# PIXRACER-FMU-R12.net
KiCad netlist of a schematic drawn in Altium Designer
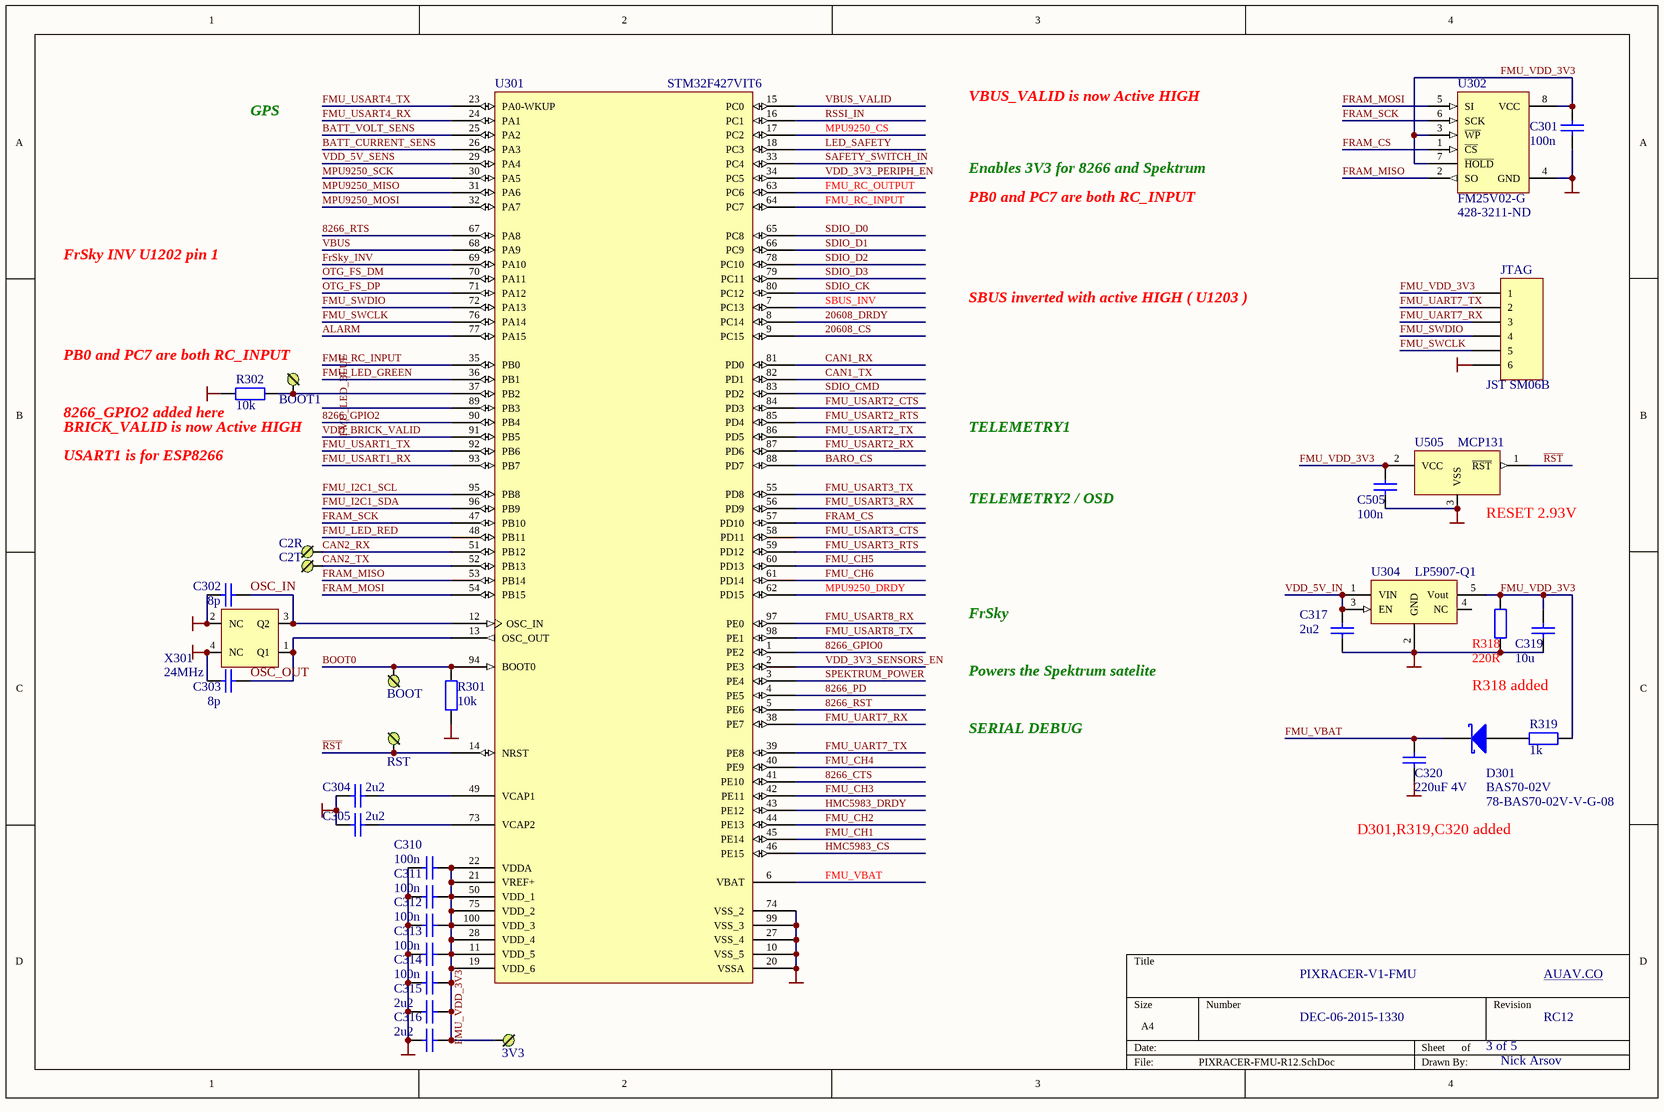
[diagram p0: PIXRACER-FMU-R12.SchDoc]

(export (version "E")
  (design (tool "Eeschema 10.0.6"))
  (components
    (comp (ref "3V3") (value "3V3") (footprint "PAD1") (libsource (lib "My_Altium") (part "PLUG")))
    (comp (ref "BOOT") (value "BOOT") (footprint "PAD1") (libsource (lib "My_Altium") (part "PLUG")))
    (comp (ref "BOOT1") (value "BOOT1") (footprint "PAD1") (libsource (lib "My_Altium") (part "PLUG")))
    (comp (ref "C2R") (value "CAN2_RX") (footprint "PAD1") (libsource (lib "My_Altium") (part "PLUG")))
    (comp (ref "C2T") (value "CAN2_TX") (footprint "PAD1") (libsource (lib "My_Altium") (part "PLUG")))
    (comp (ref "C301")
      (value "100n")
      (footprint "0402A")
      (description "Capacitor")
      (fields (field (name "PUBLISHER") "Altium Limited"))
      (libsource (lib "Miscellaneous Devices") (part "Cap"))
    )
    (comp (ref "C302")
      (value "8p")
      (footprint "0603A")
      (description "Capacitor")
      (fields (field (name "PUBLISHER") "Altium Limited"))
      (libsource (lib "Miscellaneous Devices") (part "Cap"))
    )
    (comp (ref "C303")
      (value "8p")
      (footprint "0603A")
      (description "Capacitor")
      (fields (field (name "PUBLISHER") "Altium Limited"))
      (libsource (lib "Miscellaneous Devices") (part "Cap"))
    )
    (comp (ref "C304")
      (value "2u2")
      (footprint "0402A")
      (description "Capacitor")
      (fields (field (name "PUBLISHER") "Altium Limited"))
      (libsource (lib "Miscellaneous Devices") (part "Cap"))
    )
    (comp (ref "C305")
      (value "2u2")
      (footprint "0402A")
      (description "Capacitor")
      (fields (field (name "PUBLISHER") "Altium Limited"))
      (libsource (lib "Miscellaneous Devices") (part "Cap"))
    )
    (comp (ref "C310")
      (value "100n")
      (footprint "0402A")
      (description "Capacitor")
      (fields (field (name "PUBLISHER") "Altium Limited"))
      (libsource (lib "Miscellaneous Devices") (part "Cap"))
    )
    (comp (ref "C311")
      (value "100n")
      (footprint "0402A")
      (description "Capacitor")
      (fields (field (name "PUBLISHER") "Altium Limited"))
      (libsource (lib "Miscellaneous Devices") (part "Cap"))
    )
    (comp (ref "C312")
      (value "100n")
      (footprint "0402A")
      (description "Capacitor")
      (fields (field (name "PUBLISHER") "Altium Limited"))
      (libsource (lib "Miscellaneous Devices") (part "Cap"))
    )
    (comp (ref "C313")
      (value "100n")
      (footprint "0402A")
      (description "Capacitor")
      (fields (field (name "PUBLISHER") "Altium Limited"))
      (libsource (lib "Miscellaneous Devices") (part "Cap"))
    )
    (comp (ref "C314")
      (value "100n")
      (footprint "0402A")
      (description "Capacitor")
      (fields (field (name "PUBLISHER") "Altium Limited"))
      (libsource (lib "Miscellaneous Devices") (part "Cap"))
    )
    (comp (ref "C315")
      (value "2u2")
      (footprint "0402A")
      (description "Capacitor")
      (fields (field (name "PUBLISHER") "Altium Limited"))
      (libsource (lib "Miscellaneous Devices") (part "Cap"))
    )
    (comp (ref "C316")
      (value "2u2")
      (footprint "0402A")
      (description "Capacitor")
      (fields (field (name "PUBLISHER") "Altium Limited"))
      (libsource (lib "Miscellaneous Devices") (part "Cap"))
    )
    (comp (ref "C317")
      (value "2u2")
      (footprint "0603A")
      (description "Capacitor")
      (fields (field (name "PUBLISHER") "Altium Limited"))
      (libsource (lib "Miscellaneous Devices") (part "Cap"))
    )
    (comp (ref "C319")
      (value "10u")
      (footprint "0603A")
      (description "Capacitor")
      (fields (field (name "PUBLISHER") "Altium Limited"))
      (libsource (lib "Miscellaneous Devices") (part "Cap"))
    )
    (comp (ref "C320")
      (value "220uF 4V")
      (footprint "1206A")
      (description "Capacitor")
      (fields (field (name "PUBLISHER") "Altium Limited"))
      (libsource (lib "Miscellaneous Devices") (part "Cap"))
    )
    (comp (ref "C505")
      (value "100n")
      (footprint "0402A")
      (description "Capacitor")
      (fields (field (name "PUBLISHER") "Altium Limited"))
      (libsource (lib "Miscellaneous Devices") (part "Cap"))
    )
    (comp (ref "D301")
      (value "BAS70-02V")
      (footprint "SOD-523")
      (description "Schottky Diode")
      (fields (field (name "MOUSER") "78-BAS70-02V-V-G-08") (field (name "PUBLISHER") "Altium Limited"))
      (libsource (lib "Miscellaneous Devices") (part "D Schottky"))
    )
    (comp (ref "JTAG")
      (value "JST SM06B")
      (footprint "SM06B-SRSH-TB")
      (description "Header, 6-Pin")
      (fields (field (name "PUBLISHER") "Altium Limited"))
      (libsource (lib "Miscellaneous Connectors") (part "Header 6"))
    )
    (comp (ref "R301")
      (value "10k")
      (footprint "0402A")
      (description "Resistor")
      (fields (field (name "PUBLISHER") "Altium Limited"))
      (libsource (lib "") (part "Res2_3"))
    )
    (comp (ref "R302")
      (value "10k")
      (footprint "0402A")
      (description "Resistor")
      (fields (field (name "PUBLISHER") "Altium Limited"))
      (libsource (lib "Miscellaneous Devices") (part "Res2"))
    )
    (comp (ref "R318")
      (value "220R")
      (footprint "0603A")
      (description "Resistor")
      (fields (field (name "PUBLISHER") "Altium Limited"))
      (libsource (lib "") (part "Res2_2"))
    )
    (comp (ref "R319")
      (value "1k")
      (footprint "0603A")
      (description "Resistor")
      (fields (field (name "PUBLISHER") "Altium Limited"))
      (libsource (lib "") (part "Res2_1"))
    )
    (comp (ref "RST") (value "BOOT") (footprint "PAD1") (libsource (lib "My_Altium") (part "PLUG")))
    (comp (ref "U301")
      (value "STM32F427VIT6")
      (footprint "LQFP100_L")
      (description "STM32 ARM-based 32-bit MCU with 64 Kbytes Flash, 100-pin LQFP, Industrial Temperature")
      (fields (field (name "PUBLISHER") "Altium Limited"))
      (libsource (lib "ST Microcontroller 32-Bit STM32") (part "STM32F103VBT6"))
    )
    (comp (ref "U302")
      (value "FM25V02-G")
      (footprint "SO-8_N")
      (fields (field (name "SUPPLIER PART NUMBER") "428-3211-ND"))
      (libsource (lib "My_Altium") (part "AT45DB161D-MU"))
    )
    (comp (ref "U304")
      (value "LP5907-Q1")
      (footprint "SOT23-5")
      (libsource (lib "My_Altium") (part "LP5907-Q1"))
    )
    (comp (ref "U505") (value "MCP131") (footprint "SOT-323") (libsource (lib "My_Altium") (part "MCP102")))
    (comp (ref "X301")
      (value "24MHz")
      (footprint "Crystal_2.5x2")
      (libsource (lib "My_Altium") (part "Crystal_4pin"))
    )
  )
  (nets
    (net (code "1") (name "/8266_CTS") (class "Default")
      (node (ref "U301") (pin "41") (pinfunction "PE10_41") (pintype "bidirectional"))
    )
    (net (code "2") (name "/8266_GPIO0") (class "Default")
      (node (ref "U301") (pin "1") (pinfunction "PE2_1") (pintype "bidirectional"))
    )
    (net (code "3") (name "/8266_GPIO2") (class "Default")
      (node (ref "U301") (pin "90") (pinfunction "PB4_90") (pintype "bidirectional"))
    )
    (net (code "4") (name "/8266_PD") (class "Default")
      (node (ref "U301") (pin "4") (pinfunction "PE5_4") (pintype "bidirectional"))
    )
    (net (code "5") (name "/8266_RST") (class "Default")
      (node (ref "U301") (pin "5") (pinfunction "PE6_5") (pintype "bidirectional"))
    )
    (net (code "6") (name "/8266_RTS") (class "Default")
      (node (ref "U301") (pin "67") (pinfunction "PA8_67") (pintype "bidirectional"))
    )
    (net (code "7") (name "/20608_CS") (class "Default")
      (node (ref "U301") (pin "9") (pinfunction "PC15_9") (pintype "bidirectional"))
    )
    (net (code "8") (name "/20608_DRDY") (class "Default")
      (node (ref "U301") (pin "8") (pinfunction "PC14_8") (pintype "bidirectional"))
    )
    (net (code "9") (name "/ALARM") (class "Default")
      (node (ref "U301") (pin "77") (pinfunction "PA15_77") (pintype "bidirectional"))
    )
    (net (code "10") (name "/BARO_CS") (class "Default")
      (node (ref "U301") (pin "88") (pinfunction "PD7_88") (pintype "bidirectional"))
    )
    (net (code "11") (name "/BATT_CURRENT_SENS") (class "Default")
      (node (ref "U301") (pin "26") (pinfunction "PA3_26") (pintype "bidirectional"))
    )
    (net (code "12") (name "/BATT_VOLT_SENS") (class "Default")
      (node (ref "U301") (pin "25") (pinfunction "PA2_25") (pintype "bidirectional"))
    )
    (net (code "13") (name "/BOOT0") (class "Default")
      (node (ref "BOOT") (pin "1") (pintype "passive"))
      (node (ref "R301") (pin "1") (pinfunction "1_1") (pintype "passive"))
      (node (ref "U301") (pin "94") (pinfunction "BOOT0_94") (pintype "input"))
    )
    (net (code "14") (name "/CAN1_RX") (class "Default")
      (node (ref "U301") (pin "81") (pinfunction "PD0_81") (pintype "bidirectional"))
    )
    (net (code "15") (name "/CAN1_TX") (class "Default")
      (node (ref "U301") (pin "82") (pinfunction "PD1_82") (pintype "bidirectional"))
    )
    (net (code "16") (name "/CAN2_RX") (class "Default")
      (node (ref "C2R") (pin "1") (pintype "passive"))
      (node (ref "U301") (pin "51") (pinfunction "PB12_51") (pintype "bidirectional"))
    )
    (net (code "17") (name "/CAN2_TX") (class "Default")
      (node (ref "C2T") (pin "1") (pintype "passive"))
      (node (ref "U301") (pin "52") (pinfunction "PB13_52") (pintype "bidirectional"))
    )
    (net (code "18") (name "/FMU_CH1") (class "Default")
      (node (ref "U301") (pin "45") (pinfunction "PE14_45") (pintype "bidirectional"))
    )
    (net (code "19") (name "/FMU_CH2") (class "Default")
      (node (ref "U301") (pin "44") (pinfunction "PE13_44") (pintype "bidirectional"))
    )
    (net (code "20") (name "/FMU_CH3") (class "Default")
      (node (ref "U301") (pin "42") (pinfunction "PE11_42") (pintype "bidirectional"))
    )
    (net (code "21") (name "/FMU_CH4") (class "Default")
      (node (ref "U301") (pin "40") (pinfunction "PE9_40") (pintype "bidirectional"))
    )
    (net (code "22") (name "/FMU_CH5") (class "Default")
      (node (ref "U301") (pin "60") (pinfunction "PD13_60") (pintype "bidirectional"))
    )
    (net (code "23") (name "/FMU_CH6") (class "Default")
      (node (ref "U301") (pin "61") (pinfunction "PD14_61") (pintype "bidirectional"))
    )
    (net (code "24") (name "/FMU_I2C1_SCL") (class "Default")
      (node (ref "U301") (pin "95") (pinfunction "PB8_95") (pintype "bidirectional"))
    )
    (net (code "25") (name "/FMU_I2C1_SDA") (class "Default")
      (node (ref "U301") (pin "96") (pinfunction "PB9_96") (pintype "bidirectional"))
    )
    (net (code "26") (name "/FMU_LED_BLUE") (class "Default")
      (node (ref "U301") (pin "91") (pinfunction "PB5_91") (pintype "bidirectional"))
    )
    (net (code "27") (name "/FMU_LED_GREEN") (class "Default")
      (node (ref "U301") (pin "36") (pinfunction "PB1_36") (pintype "bidirectional"))
    )
    (net (code "28") (name "/FMU_LED_RED") (class "Default")
      (node (ref "U301") (pin "48") (pinfunction "PB11_48") (pintype "bidirectional"))
    )
    (net (code "29") (name "/FMU_RC_INPUT") (class "Default")
      (node (ref "U301") (pin "35") (pinfunction "PB0_35") (pintype "bidirectional"))
      (node (ref "U301") (pin "64") (pinfunction "PC7_64") (pintype "bidirectional"))
    )
    (net (code "30") (name "/FMU_RC_OUTPUT") (class "Default")
      (node (ref "U301") (pin "63") (pinfunction "PC6_63") (pintype "bidirectional"))
    )
    (net (code "31") (name "/FMU_SWCLK") (class "Default")
      (node (ref "JTAG") (pin "5") (pinfunction "5_5") (pintype "passive"))
      (node (ref "U301") (pin "76") (pinfunction "PA14_76") (pintype "bidirectional"))
    )
    (net (code "32") (name "/FMU_SWDIO") (class "Default")
      (node (ref "JTAG") (pin "4") (pinfunction "4_4") (pintype "passive"))
      (node (ref "U301") (pin "72") (pinfunction "PA13_72") (pintype "bidirectional"))
    )
    (net (code "33") (name "/FMU_UART7_RX") (class "Default")
      (node (ref "JTAG") (pin "3") (pinfunction "3_3") (pintype "passive"))
      (node (ref "U301") (pin "38") (pinfunction "PE7_38") (pintype "bidirectional"))
    )
    (net (code "34") (name "/FMU_UART7_TX") (class "Default")
      (node (ref "JTAG") (pin "2") (pinfunction "2_2") (pintype "passive"))
      (node (ref "U301") (pin "39") (pinfunction "PE8_39") (pintype "bidirectional"))
    )
    (net (code "35") (name "/FMU_USART1_RX") (class "Default")
      (node (ref "U301") (pin "93") (pinfunction "PB7_93") (pintype "bidirectional"))
    )
    (net (code "36") (name "/FMU_USART1_TX") (class "Default")
      (node (ref "U301") (pin "92") (pinfunction "PB6_92") (pintype "bidirectional"))
    )
    (net (code "37") (name "/FMU_USART2_CTS") (class "Default")
      (node (ref "U301") (pin "84") (pinfunction "PD3_84") (pintype "bidirectional"))
    )
    (net (code "38") (name "/FMU_USART2_RTS") (class "Default")
      (node (ref "U301") (pin "85") (pinfunction "PD4_85") (pintype "bidirectional"))
    )
    (net (code "39") (name "/FMU_USART2_RX") (class "Default")
      (node (ref "U301") (pin "87") (pinfunction "PD6_87") (pintype "bidirectional"))
    )
    (net (code "40") (name "/FMU_USART2_TX") (class "Default")
      (node (ref "U301") (pin "86") (pinfunction "PD5_86") (pintype "bidirectional"))
    )
    (net (code "41") (name "/FMU_USART3_CTS") (class "Default")
      (node (ref "U301") (pin "58") (pinfunction "PD11_58") (pintype "bidirectional"))
    )
    (net (code "42") (name "/FMU_USART3_RTS") (class "Default")
      (node (ref "U301") (pin "59") (pinfunction "PD12_59") (pintype "bidirectional"))
    )
    (net (code "43") (name "/FMU_USART3_RX") (class "Default")
      (node (ref "U301") (pin "56") (pinfunction "PD9_56") (pintype "bidirectional"))
    )
    (net (code "44") (name "/FMU_USART3_TX") (class "Default")
      (node (ref "U301") (pin "55") (pinfunction "PD8_55") (pintype "bidirectional"))
    )
    (net (code "45") (name "/FMU_USART4_RX") (class "Default")
      (node (ref "U301") (pin "24") (pinfunction "PA1_24") (pintype "bidirectional"))
    )
    (net (code "46") (name "/FMU_USART4_TX") (class "Default")
      (node (ref "U301") (pin "23") (pinfunction "PA0-WKUP_23") (pintype "bidirectional"))
    )
    (net (code "47") (name "/FMU_USART8_RX") (class "Default")
      (node (ref "U301") (pin "97") (pinfunction "PE0_97") (pintype "bidirectional"))
    )
    (net (code "48") (name "/FMU_USART8_TX") (class "Default")
      (node (ref "U301") (pin "98") (pinfunction "PE1_98") (pintype "bidirectional"))
    )
    (net (code "49") (name "/FMU_VBAT") (class "Default")
      (node (ref "C320") (pin "2") (pinfunction "2_2") (pintype "passive"))
      (node (ref "D301") (pin "2") (pinfunction "K_2") (pintype "passive"))
      (node (ref "U301") (pin "6") (pinfunction "VBAT_6") (pintype "power_in"))
    )
    (net (code "50") (name "/FMU_VDD_3V3") (class "Default")
      (node (ref "3V3") (pin "1") (pintype "passive"))
      (node (ref "C301") (pin "2") (pinfunction "2_2") (pintype "passive"))
      (node (ref "C310") (pin "2") (pinfunction "2_2") (pintype "passive"))
      (node (ref "C311") (pin "2") (pinfunction "2_2") (pintype "passive"))
      (node (ref "C312") (pin "2") (pinfunction "2_2") (pintype "passive"))
      (node (ref "C313") (pin "2") (pinfunction "2_2") (pintype "passive"))
      (node (ref "C314") (pin "2") (pinfunction "2_2") (pintype "passive"))
      (node (ref "C315") (pin "2") (pinfunction "2_2") (pintype "passive"))
      (node (ref "C316") (pin "2") (pinfunction "2_2") (pintype "passive"))
      (node (ref "C319") (pin "2") (pinfunction "2_2") (pintype "passive"))
      (node (ref "C505") (pin "2") (pinfunction "2_2") (pintype "passive"))
      (node (ref "JTAG") (pin "1") (pinfunction "1_1") (pintype "passive"))
      (node (ref "R318") (pin "2") (pinfunction "2_2") (pintype "passive"))
      (node (ref "R319") (pin "1") (pinfunction "1_1") (pintype "passive"))
      (node (ref "U301") (pin "100") (pinfunction "VDD_3_100") (pintype "power_in"))
      (node (ref "U301") (pin "11") (pinfunction "VDD_5_11") (pintype "power_in"))
      (node (ref "U301") (pin "19") (pinfunction "VDD_6_19") (pintype "power_in"))
      (node (ref "U301") (pin "21") (pinfunction "VREF+_21") (pintype "power_in"))
      (node (ref "U301") (pin "22") (pinfunction "VDDA_22") (pintype "power_in"))
      (node (ref "U301") (pin "28") (pinfunction "VDD_4_28") (pintype "power_in"))
      (node (ref "U301") (pin "50") (pinfunction "VDD_1_50") (pintype "power_in"))
      (node (ref "U301") (pin "75") (pinfunction "VDD_2_75") (pintype "power_in"))
      (node (ref "U302") (pin "3") (pinfunction "~{WP}_3") (pintype "input"))
      (node (ref "U302") (pin "7") (pinfunction "~{HOLD}_7") (pintype "passive"))
      (node (ref "U302") (pin "8") (pinfunction "VCC_8") (pintype "power_in"))
      (node (ref "U304") (pin "5") (pinfunction "Vout_5") (pintype "power_in"))
      (node (ref "U505") (pin "2") (pinfunction "VCC_2") (pintype "power_in"))
    )
    (net (code "51") (name "/FRAM_CS") (class "Default")
      (node (ref "U301") (pin "57") (pinfunction "PD10_57") (pintype "bidirectional"))
      (node (ref "U302") (pin "1") (pinfunction "~{CS}_1") (pintype "input"))
    )
    (net (code "52") (name "/FRAM_MISO") (class "Default")
      (node (ref "U301") (pin "53") (pinfunction "PB14_53") (pintype "bidirectional"))
      (node (ref "U302") (pin "2") (pinfunction "SO_2") (pintype "output"))
    )
    (net (code "53") (name "/FRAM_MOSI") (class "Default")
      (node (ref "U301") (pin "54") (pinfunction "PB15_54") (pintype "bidirectional"))
      (node (ref "U302") (pin "5") (pinfunction "SI_5") (pintype "input"))
    )
    (net (code "54") (name "/FRAM_SCK") (class "Default")
      (node (ref "U301") (pin "47") (pinfunction "PB10_47") (pintype "bidirectional"))
      (node (ref "U302") (pin "6") (pinfunction "SCK_6") (pintype "input"))
    )
    (net (code "55") (name "/FrSky_INV") (class "Default")
      (node (ref "U301") (pin "69") (pinfunction "PA10_69") (pintype "bidirectional"))
    )
    (net (code "56") (name "/HMC5983_CS") (class "Default")
      (node (ref "U301") (pin "46") (pinfunction "PE15_46") (pintype "bidirectional"))
    )
    (net (code "57") (name "/HMC5983_DRDY") (class "Default")
      (node (ref "U301") (pin "43") (pinfunction "PE12_43") (pintype "bidirectional"))
    )
    (net (code "58") (name "/LED_SAFETY") (class "Default")
      (node (ref "U301") (pin "18") (pinfunction "PC3_18") (pintype "bidirectional"))
    )
    (net (code "59") (name "/MPU9250_CS") (class "Default")
      (node (ref "U301") (pin "17") (pinfunction "PC2_17") (pintype "bidirectional"))
    )
    (net (code "60") (name "/MPU9250_DRDY") (class "Default")
      (node (ref "U301") (pin "62") (pinfunction "PD15_62") (pintype "bidirectional"))
    )
    (net (code "61") (name "/MPU9250_MISO") (class "Default")
      (node (ref "U301") (pin "31") (pinfunction "PA6_31") (pintype "bidirectional"))
    )
    (net (code "62") (name "/MPU9250_MOSI") (class "Default")
      (node (ref "U301") (pin "32") (pinfunction "PA7_32") (pintype "bidirectional"))
    )
    (net (code "63") (name "/MPU9250_SCK") (class "Default")
      (node (ref "U301") (pin "30") (pinfunction "PA5_30") (pintype "bidirectional"))
    )
    (net (code "64") (name "/OSC_IN") (class "Default")
      (node (ref "C302") (pin "2") (pinfunction "2_2") (pintype "passive"))
      (node (ref "U301") (pin "12") (pinfunction "OSC_IN_12") (pintype "input"))
      (node (ref "X301") (pin "3") (pinfunction "Q2_3") (pintype "passive"))
    )
    (net (code "65") (name "/OSC_OUT") (class "Default")
      (node (ref "C303") (pin "2") (pinfunction "2_2") (pintype "passive"))
      (node (ref "U301") (pin "13") (pinfunction "OSC_OUT_13") (pintype "output"))
      (node (ref "X301") (pin "1") (pinfunction "Q1_1") (pintype "passive"))
    )
    (net (code "66") (name "/OTG_FS_DM") (class "Default")
      (node (ref "U301") (pin "70") (pinfunction "PA11_70") (pintype "bidirectional"))
    )
    (net (code "67") (name "/OTG_FS_DP") (class "Default")
      (node (ref "U301") (pin "71") (pinfunction "PA12_71") (pintype "bidirectional"))
    )
    (net (code "68") (name "/RSSI_IN") (class "Default")
      (node (ref "U301") (pin "16") (pinfunction "PC1_16") (pintype "bidirectional"))
    )
    (net (code "69") (name "/SAFETY_SWITCH_IN") (class "Default")
      (node (ref "U301") (pin "33") (pinfunction "PC4_33") (pintype "bidirectional"))
    )
    (net (code "70") (name "/SBUS_INV") (class "Default")
      (node (ref "U301") (pin "7") (pinfunction "PC13_7") (pintype "bidirectional"))
    )
    (net (code "71") (name "/SDIO_CK") (class "Default")
      (node (ref "U301") (pin "80") (pinfunction "PC12_80") (pintype "bidirectional"))
    )
    (net (code "72") (name "/SDIO_CMD") (class "Default")
      (node (ref "U301") (pin "83") (pinfunction "PD2_83") (pintype "bidirectional"))
    )
    (net (code "73") (name "/SDIO_D0") (class "Default")
      (node (ref "U301") (pin "65") (pinfunction "PC8_65") (pintype "bidirectional"))
    )
    (net (code "74") (name "/SDIO_D1") (class "Default")
      (node (ref "U301") (pin "66") (pinfunction "PC9_66") (pintype "bidirectional"))
    )
    (net (code "75") (name "/SDIO_D2") (class "Default")
      (node (ref "U301") (pin "78") (pinfunction "PC10_78") (pintype "bidirectional"))
    )
    (net (code "76") (name "/SDIO_D3") (class "Default")
      (node (ref "U301") (pin "79") (pinfunction "PC11_79") (pintype "bidirectional"))
    )
    (net (code "77") (name "/SPEKTRUM_POWER") (class "Default")
      (node (ref "U301") (pin "3") (pinfunction "PE4_3") (pintype "bidirectional"))
    )
    (net (code "78") (name "/VBUS") (class "Default")
      (node (ref "U301") (pin "68") (pinfunction "PA9_68") (pintype "bidirectional"))
    )
    (net (code "79") (name "/VBUS_VALID") (class "Default")
      (node (ref "U301") (pin "15") (pinfunction "PC0_15") (pintype "bidirectional"))
    )
    (net (code "80") (name "/VDD_3V3_PERIPH_EN") (class "Default")
      (node (ref "U301") (pin "34") (pinfunction "PC5_34") (pintype "bidirectional"))
    )
    (net (code "81") (name "/VDD_3V3_SENSORS_EN") (class "Default")
      (node (ref "U301") (pin "2") (pinfunction "PE3_2") (pintype "bidirectional"))
    )
    (net (code "82") (name "/VDD_5V_IN") (class "Default")
      (node (ref "C317") (pin "2") (pinfunction "2_2") (pintype "passive"))
      (node (ref "U304") (pin "1") (pinfunction "VIN_1") (pintype "power_in"))
      (node (ref "U304") (pin "3") (pinfunction "EN_3") (pintype "input"))
    )
    (net (code "83") (name "/VDD_5V_SENS") (class "Default")
      (node (ref "U301") (pin "29") (pinfunction "PA4_29") (pintype "bidirectional"))
    )
    (net (code "84") (name "/~{RST}") (class "Default")
      (node (ref "RST") (pin "1") (pintype "passive"))
      (node (ref "U301") (pin "14") (pinfunction "NRST_14") (pintype "bidirectional"))
      (node (ref "U505") (pin "1") (pinfunction "~{RST}_1") (pintype "output"))
    )
    (net (code "85") (name "GND") (class "Default")
      (node (ref "C301") (pin "1") (pinfunction "1_1") (pintype "passive"))
      (node (ref "C302") (pin "1") (pinfunction "1_1") (pintype "passive"))
      (node (ref "C303") (pin "1") (pinfunction "1_1") (pintype "passive"))
      (node (ref "C304") (pin "2") (pinfunction "2_2") (pintype "passive"))
      (node (ref "C305") (pin "2") (pinfunction "2_2") (pintype "passive"))
      (node (ref "C310") (pin "1") (pinfunction "1_1") (pintype "passive"))
      (node (ref "C311") (pin "1") (pinfunction "1_1") (pintype "passive"))
      (node (ref "C312") (pin "1") (pinfunction "1_1") (pintype "passive"))
      (node (ref "C313") (pin "1") (pinfunction "1_1") (pintype "passive"))
      (node (ref "C314") (pin "1") (pinfunction "1_1") (pintype "passive"))
      (node (ref "C315") (pin "1") (pinfunction "1_1") (pintype "passive"))
      (node (ref "C316") (pin "1") (pinfunction "1_1") (pintype "passive"))
      (node (ref "C317") (pin "1") (pinfunction "1_1") (pintype "passive"))
      (node (ref "C319") (pin "1") (pinfunction "1_1") (pintype "passive"))
      (node (ref "C320") (pin "1") (pinfunction "1_1") (pintype "passive"))
      (node (ref "C505") (pin "1") (pinfunction "1_1") (pintype "passive"))
      (node (ref "JTAG") (pin "6") (pinfunction "6_6") (pintype "passive"))
      (node (ref "R301") (pin "2") (pinfunction "2_2") (pintype "passive"))
      (node (ref "R302") (pin "1") (pinfunction "1_1") (pintype "passive"))
      (node (ref "R318") (pin "1") (pinfunction "1_1") (pintype "passive"))
      (node (ref "U301") (pin "10") (pinfunction "VSS_5_10") (pintype "power_in"))
      (node (ref "U301") (pin "20") (pinfunction "VSSA_20") (pintype "power_in"))
      (node (ref "U301") (pin "27") (pinfunction "VSS_4_27") (pintype "power_in"))
      (node (ref "U301") (pin "74") (pinfunction "VSS_2_74") (pintype "power_in"))
      (node (ref "U301") (pin "99") (pinfunction "VSS_3_99") (pintype "power_in"))
      (node (ref "U302") (pin "4") (pinfunction "GND_4") (pintype "power_in"))
      (node (ref "U304") (pin "2") (pinfunction "GND_2") (pintype "power_in"))
      (node (ref "U505") (pin "3") (pinfunction "VSS_3") (pintype "power_in"))
      (node (ref "X301") (pin "2") (pinfunction "NC_2") (pintype "passive"))
      (node (ref "X301") (pin "4") (pinfunction "NC_4") (pintype "passive"))
    )
    (net (code "86") (name "Net-(D301-A)") (class "Default")
      (node (ref "D301") (pin "1") (pinfunction "A_1") (pintype "passive"))
      (node (ref "R319") (pin "2") (pinfunction "2_2") (pintype "passive"))
    )
    (net (code "87") (name "Net-(U301-PB2)") (class "Default")
      (node (ref "BOOT1") (pin "1") (pintype "passive"))
      (node (ref "R302") (pin "2") (pinfunction "2_2") (pintype "passive"))
      (node (ref "U301") (pin "37") (pinfunction "PB2_37") (pintype "bidirectional"))
    )
    (net (code "88") (name "Net-(U301-VCAP1)") (class "Default")
      (node (ref "C304") (pin "1") (pinfunction "1_1") (pintype "passive"))
      (node (ref "U301") (pin "49") (pinfunction "VCAP1_49") (pintype "passive"))
    )
    (net (code "89") (name "Net-(U301-VCAP2)") (class "Default")
      (node (ref "C305") (pin "1") (pinfunction "1_1") (pintype "passive"))
      (node (ref "U301") (pin "73") (pinfunction "VCAP2_73") (pintype "passive"))
    )
    (net (code "90") (name "unconnected-(U301-PB3-Pad89)") (class "Default")
      (node (ref "U301") (pin "89") (pinfunction "PB3_89") (pintype "bidirectional"))
    )
    (net (code "91") (name "unconnected-(U304-NC-Pad4)") (class "Default")
      (node (ref "U304") (pin "4") (pinfunction "NC_4") (pintype "passive"))
    )
  )
)
